# EV_Safety_Board.net
KiCad netlist of a schematic drawn in EAGLE
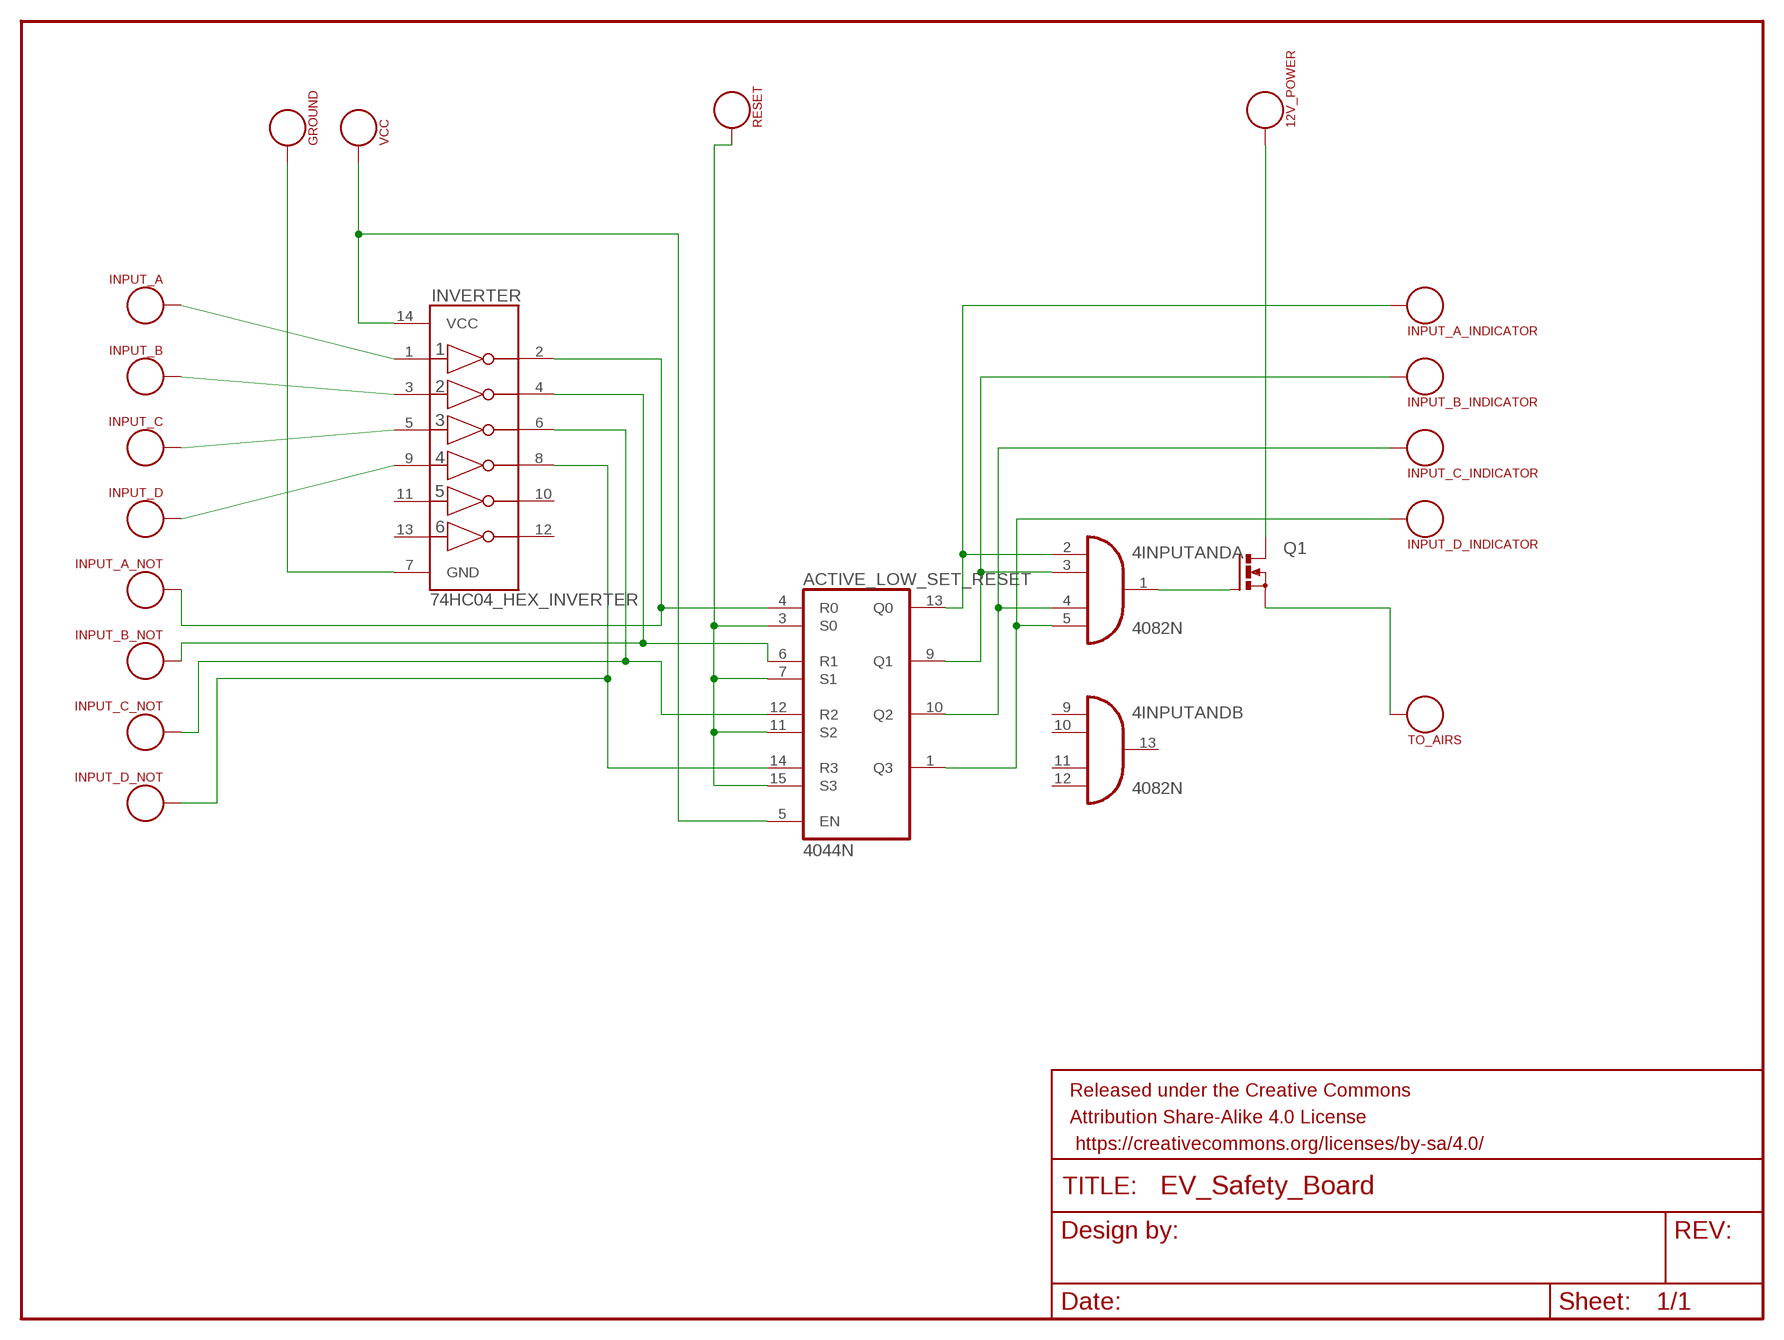
[diagram p0: schematic, sheet 1]

(export (version "E")
  (design (tool "Eeschema 10.0.6"))
  (components
    (comp (ref "4INPUTAND")
      (value "4082N")
      (footprint "eagle-import:DIL14")
      (libsource (lib "eagle-import") (part "4082N"))
    )
    (comp (ref "12V_POWER")
      (value "SEW_HOLE")
      (footprint "eagle-import:SIMPLE_HOLE")
      (libsource (lib "eagle-import") (part "SEW_HOLE"))
    )
    (comp (ref "ACTIVE_LOW_SET_RESET")
      (value "4044N")
      (footprint "eagle-import:DIL16")
      (libsource (lib "eagle-import") (part "4044N"))
    )
    (comp (ref "FRAME1")
      (value "FRAME-LETTERNO_PACKAGE")
      (footprint "eagle-import:DUMMY")
      (fields (field (name "DESIGNER") "Nobody"))
      (libsource (lib "eagle-import") (part "FRAME-LETTERNO_PACKAGE"))
    )
    (comp (ref "GROUND")
      (value "SEW_HOLE")
      (footprint "eagle-import:SIMPLE_HOLE")
      (libsource (lib "eagle-import") (part "SEW_HOLE"))
    )
    (comp (ref "INPUT_A")
      (value "SEW_HOLE")
      (footprint "eagle-import:SIMPLE_HOLE")
      (libsource (lib "eagle-import") (part "SEW_HOLE"))
    )
    (comp (ref "INPUT_A_INDICATOR")
      (value "SEW_HOLE")
      (footprint "eagle-import:SIMPLE_HOLE")
      (libsource (lib "eagle-import") (part "SEW_HOLE"))
    )
    (comp (ref "INPUT_A_NOT")
      (value "SEW_HOLE")
      (footprint "eagle-import:SIMPLE_HOLE")
      (libsource (lib "eagle-import") (part "SEW_HOLE"))
    )
    (comp (ref "INPUT_B")
      (value "SEW_HOLE")
      (footprint "eagle-import:SIMPLE_HOLE")
      (libsource (lib "eagle-import") (part "SEW_HOLE"))
    )
    (comp (ref "INPUT_B_INDICATOR")
      (value "SEW_HOLE")
      (footprint "eagle-import:SIMPLE_HOLE")
      (libsource (lib "eagle-import") (part "SEW_HOLE"))
    )
    (comp (ref "INPUT_B_NOT")
      (value "SEW_HOLE")
      (footprint "eagle-import:SIMPLE_HOLE")
      (libsource (lib "eagle-import") (part "SEW_HOLE"))
    )
    (comp (ref "INPUT_C")
      (value "SEW_HOLE")
      (footprint "eagle-import:SIMPLE_HOLE")
      (libsource (lib "eagle-import") (part "SEW_HOLE"))
    )
    (comp (ref "INPUT_C_INDICATOR")
      (value "SEW_HOLE")
      (footprint "eagle-import:SIMPLE_HOLE")
      (libsource (lib "eagle-import") (part "SEW_HOLE"))
    )
    (comp (ref "INPUT_C_NOT")
      (value "SEW_HOLE")
      (footprint "eagle-import:SIMPLE_HOLE")
      (libsource (lib "eagle-import") (part "SEW_HOLE"))
    )
    (comp (ref "INPUT_D")
      (value "SEW_HOLE")
      (footprint "eagle-import:SIMPLE_HOLE")
      (libsource (lib "eagle-import") (part "SEW_HOLE"))
    )
    (comp (ref "INPUT_D_INDICATOR")
      (value "SEW_HOLE")
      (footprint "eagle-import:SIMPLE_HOLE")
      (libsource (lib "eagle-import") (part "SEW_HOLE"))
    )
    (comp (ref "INPUT_D_NOT")
      (value "SEW_HOLE")
      (footprint "eagle-import:SIMPLE_HOLE")
      (libsource (lib "eagle-import") (part "SEW_HOLE"))
    )
    (comp (ref "INVERTER")
      (value "74HC04_HEX_INVERTER")
      (footprint "eagle-import:DIL14")
      (libsource (lib "eagle-import") (part "74HC04_HEX_INVERTER"))
    )
    (comp (ref "Q1")
      (value "PMOSFET_NTO220BH")
      (footprint "eagle-import:TO220BH")
      (libsource (lib "eagle-import") (part "PMOSFET_NTO220BH"))
    )
    (comp (ref "RESET")
      (value "SEW_HOLE")
      (footprint "eagle-import:SIMPLE_HOLE")
      (libsource (lib "eagle-import") (part "SEW_HOLE"))
    )
    (comp (ref "TO_AIRS")
      (value "SEW_HOLE")
      (footprint "eagle-import:SIMPLE_HOLE")
      (libsource (lib "eagle-import") (part "SEW_HOLE"))
    )
    (comp (ref "VCC")
      (value "SEW_HOLE")
      (footprint "eagle-import:SIMPLE_HOLE")
      (libsource (lib "eagle-import") (part "SEW_HOLE"))
    )
  )
  (nets
    (net (code "1") (name "Net-(4INPUTANDA-I0)") (class "Default")
      (node (ref "4INPUTAND") (pin "2") (pinfunction "I0_2") (pintype "input"))
      (node (ref "ACTIVE_LOW_SET_RESET") (pin "13") (pinfunction "Q0_13") (pintype "output"))
      (node (ref "INPUT_A_INDICATOR") (pin "P$1") (pinfunction "P$1_P$1") (pintype "bidirectional"))
    )
    (net (code "2") (name "Net-(4INPUTANDA-I1)") (class "Default")
      (node (ref "4INPUTAND") (pin "3") (pinfunction "I1_3") (pintype "input"))
      (node (ref "ACTIVE_LOW_SET_RESET") (pin "9") (pinfunction "Q1_9") (pintype "output"))
      (node (ref "INPUT_B_INDICATOR") (pin "P$1") (pinfunction "P$1_P$1") (pintype "bidirectional"))
    )
    (net (code "3") (name "Net-(4INPUTANDA-I2)") (class "Default")
      (node (ref "4INPUTAND") (pin "4") (pinfunction "I2_4") (pintype "input"))
      (node (ref "ACTIVE_LOW_SET_RESET") (pin "10") (pinfunction "Q2_10") (pintype "output"))
      (node (ref "INPUT_C_INDICATOR") (pin "P$1") (pinfunction "P$1_P$1") (pintype "bidirectional"))
    )
    (net (code "4") (name "Net-(4INPUTANDA-I3)") (class "Default")
      (node (ref "4INPUTAND") (pin "5") (pinfunction "I3_5") (pintype "input"))
      (node (ref "ACTIVE_LOW_SET_RESET") (pin "1") (pinfunction "Q3_1") (pintype "output"))
      (node (ref "INPUT_D_INDICATOR") (pin "P$1") (pinfunction "P$1_P$1") (pintype "bidirectional"))
    )
    (net (code "5") (name "Net-(4INPUTANDA-O)") (class "Default")
      (node (ref "4INPUTAND") (pin "1") (pinfunction "O_1") (pintype "output"))
      (node (ref "Q1") (pin "G") (pinfunction "G_G") (pintype "passive"))
    )
    (net (code "6") (name "Net-(12V_POWER-PadP$1)") (class "Default")
      (node (ref "12V_POWER") (pin "P$1") (pinfunction "P$1_P$1") (pintype "bidirectional"))
      (node (ref "Q1") (pin "D") (pinfunction "D_D") (pintype "passive"))
    )
    (net (code "7") (name "Net-(ACTIVE_LOW_SET_RESETA-EN)") (class "Default")
      (node (ref "ACTIVE_LOW_SET_RESET") (pin "5") (pinfunction "EN_5") (pintype "input"))
      (node (ref "INVERTER") (pin "14") (pinfunction "VCC_14") (pintype "power_in"))
      (node (ref "VCC") (pin "P$1") (pinfunction "P$1_P$1") (pintype "bidirectional"))
    )
    (net (code "8") (name "Net-(ACTIVE_LOW_SET_RESETA-R0)") (class "Default")
      (node (ref "ACTIVE_LOW_SET_RESET") (pin "4") (pinfunction "R0_4") (pintype "input"))
      (node (ref "INPUT_A_NOT") (pin "P$1") (pinfunction "P$1_P$1") (pintype "bidirectional"))
      (node (ref "INVERTER") (pin "2") (pinfunction "1Y_2") (pintype "output"))
    )
    (net (code "9") (name "Net-(ACTIVE_LOW_SET_RESETA-R1)") (class "Default")
      (node (ref "ACTIVE_LOW_SET_RESET") (pin "6") (pinfunction "R1_6") (pintype "input"))
      (node (ref "INPUT_B_NOT") (pin "P$1") (pinfunction "P$1_P$1") (pintype "bidirectional"))
      (node (ref "INVERTER") (pin "4") (pinfunction "2Y_4") (pintype "output"))
    )
    (net (code "10") (name "Net-(ACTIVE_LOW_SET_RESETA-R2)") (class "Default")
      (node (ref "ACTIVE_LOW_SET_RESET") (pin "12") (pinfunction "R2_12") (pintype "input"))
      (node (ref "INPUT_C_NOT") (pin "P$1") (pinfunction "P$1_P$1") (pintype "bidirectional"))
      (node (ref "INVERTER") (pin "6") (pinfunction "3Y_6") (pintype "output"))
    )
    (net (code "11") (name "Net-(ACTIVE_LOW_SET_RESETA-R3)") (class "Default")
      (node (ref "ACTIVE_LOW_SET_RESET") (pin "14") (pinfunction "R3_14") (pintype "input"))
      (node (ref "INPUT_D_NOT") (pin "P$1") (pinfunction "P$1_P$1") (pintype "bidirectional"))
      (node (ref "INVERTER") (pin "8") (pinfunction "4Y_8") (pintype "output"))
    )
    (net (code "12") (name "Net-(ACTIVE_LOW_SET_RESETA-S0)") (class "Default")
      (node (ref "ACTIVE_LOW_SET_RESET") (pin "11") (pinfunction "S2_11") (pintype "input"))
      (node (ref "ACTIVE_LOW_SET_RESET") (pin "15") (pinfunction "S3_15") (pintype "input"))
      (node (ref "ACTIVE_LOW_SET_RESET") (pin "3") (pinfunction "S0_3") (pintype "input"))
      (node (ref "ACTIVE_LOW_SET_RESET") (pin "7") (pinfunction "S1_7") (pintype "input"))
      (node (ref "RESET") (pin "P$1") (pinfunction "P$1_P$1") (pintype "bidirectional"))
    )
    (net (code "13") (name "Net-(INVERTER-1A)") (class "Default")
      (node (ref "INPUT_A") (pin "P$1") (pinfunction "P$1_P$1") (pintype "bidirectional"))
      (node (ref "INVERTER") (pin "1") (pinfunction "1A_1") (pintype "input"))
    )
    (net (code "14") (name "Net-(INVERTER-2A)") (class "Default")
      (node (ref "INPUT_B") (pin "P$1") (pinfunction "P$1_P$1") (pintype "bidirectional"))
      (node (ref "INVERTER") (pin "3") (pinfunction "2A_3") (pintype "input"))
    )
    (net (code "15") (name "Net-(INVERTER-3A)") (class "Default")
      (node (ref "INPUT_C") (pin "P$1") (pinfunction "P$1_P$1") (pintype "bidirectional"))
      (node (ref "INVERTER") (pin "5") (pinfunction "3A_5") (pintype "input"))
    )
    (net (code "16") (name "Net-(INVERTER-4A)") (class "Default")
      (node (ref "INPUT_D") (pin "P$1") (pinfunction "P$1_P$1") (pintype "bidirectional"))
      (node (ref "INVERTER") (pin "9") (pinfunction "4A_9") (pintype "input"))
    )
    (net (code "17") (name "Net-(INVERTER-GND)") (class "Default")
      (node (ref "GROUND") (pin "P$1") (pinfunction "P$1_P$1") (pintype "bidirectional"))
      (node (ref "INVERTER") (pin "7") (pinfunction "GND_7") (pintype "power_in"))
    )
    (net (code "18") (name "Net-(Q1-PadS)") (class "Default")
      (node (ref "Q1") (pin "S") (pinfunction "S_S") (pintype "passive"))
      (node (ref "TO_AIRS") (pin "P$1") (pinfunction "P$1_P$1") (pintype "bidirectional"))
    )
    (net (code "19") (name "unconnected-(4INPUTANDB-I0-Pad9)") (class "Default")
      (node (ref "4INPUTAND") (pin "9") (pinfunction "I0_9") (pintype "input"))
    )
    (net (code "20") (name "unconnected-(4INPUTANDB-I1-Pad10)") (class "Default")
      (node (ref "4INPUTAND") (pin "10") (pinfunction "I1_10") (pintype "input"))
    )
    (net (code "21") (name "unconnected-(4INPUTANDB-I2-Pad11)") (class "Default")
      (node (ref "4INPUTAND") (pin "11") (pinfunction "I2_11") (pintype "input"))
    )
    (net (code "22") (name "unconnected-(4INPUTANDB-I3-Pad12)") (class "Default")
      (node (ref "4INPUTAND") (pin "12") (pinfunction "I3_12") (pintype "input"))
    )
    (net (code "23") (name "unconnected-(4INPUTANDB-O-Pad13)") (class "Default")
      (node (ref "4INPUTAND") (pin "13") (pinfunction "O_13") (pintype "output"))
    )
    (net (code "24") (name "unconnected-(INVERTER-5A-Pad11)") (class "Default")
      (node (ref "INVERTER") (pin "11") (pinfunction "5A_11") (pintype "input"))
    )
    (net (code "25") (name "unconnected-(INVERTER-5Y-Pad10)") (class "Default")
      (node (ref "INVERTER") (pin "10") (pinfunction "5Y_10") (pintype "output"))
    )
    (net (code "26") (name "unconnected-(INVERTER-6A-Pad13)") (class "Default")
      (node (ref "INVERTER") (pin "13") (pinfunction "6A_13") (pintype "input"))
    )
    (net (code "27") (name "unconnected-(INVERTER-6Y-Pad12)") (class "Default")
      (node (ref "INVERTER") (pin "12") (pinfunction "6Y_12") (pintype "output"))
    )
  )
)
